# nm_main.net
KiCad netlist of a schematic drawn in Altium Designer
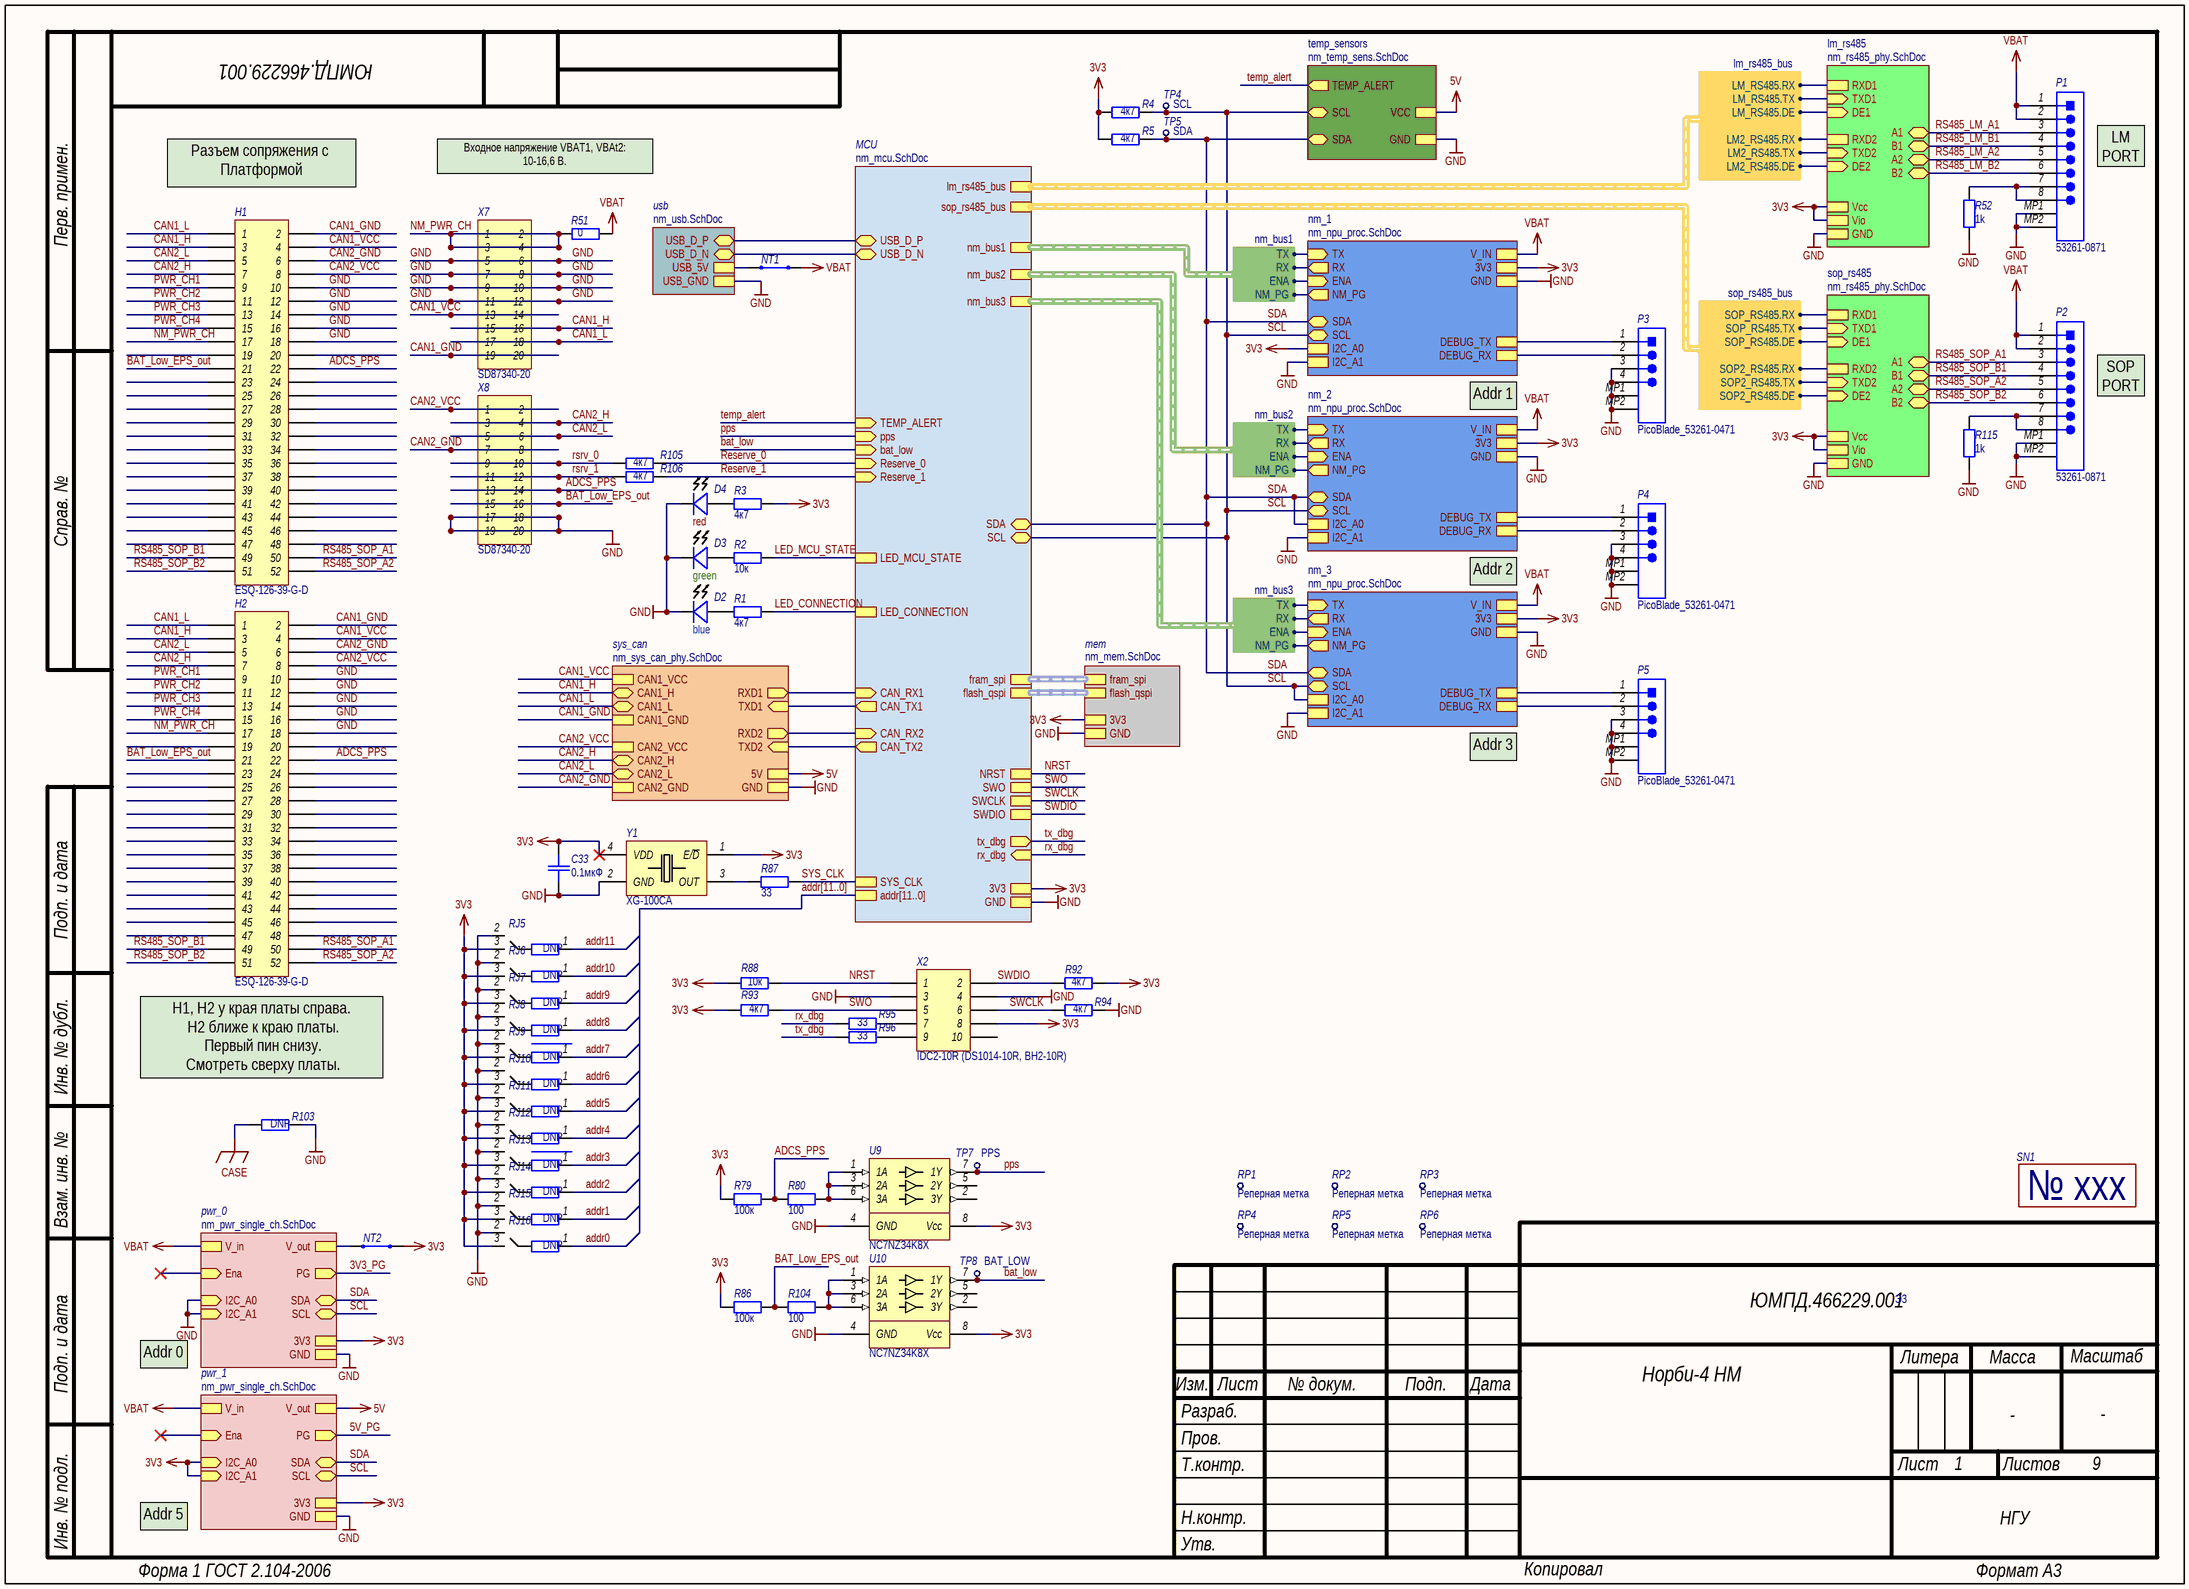
[diagram p0: nm_main.SchDoc]

(export (version "E")
  (design (tool "Eeschema 10.0.6"))
  (components
    (comp (ref "C33")
      (value "0.1мкФ")
      (footprint "SMD_C0603")
      (description "Capacitor")
      (libsource (lib "Passive") (part "Capacitor"))
    )
    (comp (ref "D2")
      (value "blue")
      (footprint "LED_0603")
      (fields (field (name "Comment") "LED"))
      (libsource (lib "LED") (part "LED"))
    )
    (comp (ref "D3")
      (value "green")
      (footprint "LED_0603")
      (fields (field (name "Comment") "LED"))
      (libsource (lib "LED") (part "LED"))
    )
    (comp (ref "D4")
      (value "red")
      (footprint "LED_0603")
      (fields (field (name "Comment") "LED"))
      (libsource (lib "LED") (part "LED"))
    )
    (comp (ref "H1")
      (value "ESQ-126-39-G-D")
      (footprint "ESQ-126-39-G-D")
      (description "Elevated socket, dual-row, 26-pin per row")
      (fields (field (name "НАИМЕНОВАНИЕ") "ESQ-126-39-G-D"))
      (libsource (lib "Connector") (part "ESQ-126-39-G-D"))
    )
    (comp (ref "H2")
      (value "ESQ-126-39-G-D")
      (footprint "ESQ-126-39-G-D")
      (description "Elevated socket, dual-row, 26-pin per row")
      (fields (field (name "НАИМЕНОВАНИЕ") "ESQ-126-39-G-D"))
      (libsource (lib "Connector") (part "ESQ-126-39-G-D"))
    )
    (comp (ref "NT1")
      (value "OSM R1-8")
      (footprint "NetTie_1mm")
      (description "Different Nets connection")
      (libsource (lib "Passive") (part "NetTie"))
    )
    (comp (ref "NT2")
      (value "OSM R1-8")
      (footprint "NetTie_1mm")
      (description "Different Nets connection")
      (libsource (lib "Passive") (part "NetTie"))
    )
    (comp (ref "P1")
      (value "53261-0871")
      (footprint "53261-0871")
      (description "Male Header, Pitch 1.25 mm, 1 x 8 Position, Height 3.4 mm, -40 to 85 degC, RoHS, Tape and Reel")
      (fields (field (name "НАИМЕНОВАНИЕ") "53261-0871"))
      (libsource (lib "Connector") (part "PicoBlade_53261-0871"))
    )
    (comp (ref "P2")
      (value "53261-0871")
      (footprint "53261-0871")
      (description "Male Header, Pitch 1.25 mm, 1 x 8 Position, Height 3.4 mm, -40 to 85 degC, RoHS, Tape and Reel")
      (fields (field (name "НАИМЕНОВАНИЕ") "53261-0871"))
      (libsource (lib "Connector") (part "PicoBlade_53261-0871"))
    )
    (comp (ref "P3")
      (value "PicoBlade_53261-0471")
      (footprint "53261-0471")
      (description "Male Header, Pitch 1.25 mm, 1 x 4 Position, Height 3.4 mm, -40 to 85 degC, RoHS, Tape and Reel")
      (libsource (lib "Connector") (part "PicoBlade_53261-0471"))
    )
    (comp (ref "P4")
      (value "PicoBlade_53261-0471")
      (footprint "53261-0471")
      (description "Male Header, Pitch 1.25 mm, 1 x 4 Position, Height 3.4 mm, -40 to 85 degC, RoHS, Tape and Reel")
      (libsource (lib "Connector") (part "PicoBlade_53261-0471"))
    )
    (comp (ref "P5")
      (value "PicoBlade_53261-0471")
      (footprint "53261-0471")
      (description "Male Header, Pitch 1.25 mm, 1 x 4 Position, Height 3.4 mm, -40 to 85 degC, RoHS, Tape and Reel")
      (libsource (lib "Connector") (part "PicoBlade_53261-0471"))
    )
    (comp (ref "R1")
      (value "4к7")
      (footprint "SMD_0603")
      (description "Resistor")
      (libsource (lib "") (part "Resistor_3"))
    )
    (comp (ref "R2")
      (value "10к")
      (footprint "SMD_0603")
      (description "Resistor")
      (libsource (lib "") (part "Resistor_3"))
    )
    (comp (ref "R3")
      (value "4к7")
      (footprint "SMD_0603")
      (description "Resistor")
      (libsource (lib "") (part "Resistor_3"))
    )
    (comp (ref "R4")
      (value "4к7")
      (footprint "SMD_0603")
      (description "Resistor")
      (libsource (lib "") (part "Resistor_1"))
    )
    (comp (ref "R5")
      (value "4к7")
      (footprint "SMD_0603")
      (description "Resistor")
      (libsource (lib "") (part "Resistor_1"))
    )
    (comp (ref "R51")
      (value "0")
      (footprint "SMD_1206")
      (description "Resistor")
      (libsource (lib "Passive") (part "Resistor"))
    )
    (comp (ref "R52")
      (value "1k")
      (footprint "SMD_0603")
      (description "Resistor")
      (libsource (lib "") (part "Resistor_2"))
    )
    (comp (ref "R79")
      (value "100к")
      (footprint "SMD_0603")
      (description "Resistor")
      (libsource (lib "Passive") (part "Resistor"))
    )
    (comp (ref "R80")
      (value "100")
      (footprint "SMD_0603")
      (description "Resistor")
      (libsource (lib "Passive") (part "Resistor"))
    )
    (comp (ref "R86")
      (value "100к")
      (footprint "SMD_0603")
      (description "Resistor")
      (libsource (lib "Passive") (part "Resistor"))
    )
    (comp (ref "R87")
      (value "33")
      (footprint "SMD_0603")
      (description "Resistor")
      (libsource (lib "") (part "Resistor_2"))
    )
    (comp (ref "R88")
      (value "10к")
      (footprint "SMD_0603")
      (description "Resistor")
      (libsource (lib "Passive") (part "Resistor"))
    )
    (comp (ref "R92")
      (value "4к7")
      (footprint "SMD_0603")
      (description "Resistor")
      (libsource (lib "") (part "Resistor_2"))
    )
    (comp (ref "R93")
      (value "4к7")
      (footprint "SMD_0603")
      (description "Resistor")
      (libsource (lib "") (part "Resistor_1"))
    )
    (comp (ref "R94")
      (value "4к7")
      (footprint "SMD_0603")
      (description "Resistor")
      (libsource (lib "") (part "Resistor_1"))
    )
    (comp (ref "R95")
      (value "33")
      (footprint "SMD_0603")
      (description "Resistor")
      (libsource (lib "") (part "Resistor_2"))
    )
    (comp (ref "R96")
      (value "33")
      (footprint "SMD_0603")
      (description "Resistor")
      (libsource (lib "") (part "Resistor_2"))
    )
    (comp (ref "R103")
      (value "DNP")
      (footprint "SMD_0805")
      (description "Resistor")
      (libsource (lib "") (part "Resistor_1"))
    )
    (comp (ref "R104")
      (value "100")
      (footprint "SMD_0603")
      (description "Resistor")
      (libsource (lib "Passive") (part "Resistor"))
    )
    (comp (ref "R105")
      (value "4к7")
      (footprint "SMD_0603")
      (description "Resistor")
      (libsource (lib "") (part "Resistor_3"))
    )
    (comp (ref "R106")
      (value "4к7")
      (footprint "SMD_0603")
      (description "Resistor")
      (libsource (lib "") (part "Resistor_3"))
    )
    (comp (ref "R115")
      (value "1k")
      (footprint "SMD_0603")
      (description "Resistor")
      (libsource (lib "") (part "Resistor_2"))
    )
    (comp (ref "RJ5")
      (value "DNP")
      (footprint "SMD_JMP_0402")
      (description "Resistor-Jumper")
      (fields (field (name "Comment") "OSM R1-8"))
      (libsource (lib "Passive") (part "Resistor_Jamper"))
    )
    (comp (ref "RJ6")
      (value "DNP")
      (footprint "SMD_JMP_0402")
      (description "Resistor-Jumper")
      (fields (field (name "Comment") "OSM R1-8"))
      (libsource (lib "Passive") (part "Resistor_Jamper"))
    )
    (comp (ref "RJ7")
      (value "DNP")
      (footprint "SMD_JMP_0402")
      (description "Resistor-Jumper")
      (fields (field (name "Comment") "OSM R1-8"))
      (libsource (lib "Passive") (part "Resistor_Jamper"))
    )
    (comp (ref "RJ8")
      (value "DNP")
      (footprint "SMD_JMP_0402")
      (description "Resistor-Jumper")
      (fields (field (name "Comment") "OSM R1-8"))
      (libsource (lib "Passive") (part "Resistor_Jamper"))
    )
    (comp (ref "RJ9")
      (value "DNP")
      (footprint "SMD_JMP_0402")
      (description "Resistor-Jumper")
      (fields (field (name "Comment") "OSM R1-8"))
      (libsource (lib "Passive") (part "Resistor_Jamper"))
    )
    (comp (ref "RJ10")
      (value "DNP")
      (footprint "SMD_JMP_0402")
      (description "Resistor-Jumper")
      (fields (field (name "Comment") "OSM R1-8"))
      (libsource (lib "Passive") (part "Resistor_Jamper"))
    )
    (comp (ref "RJ11")
      (value "DNP")
      (footprint "SMD_JMP_0402")
      (description "Resistor-Jumper")
      (fields (field (name "Comment") "OSM R1-8"))
      (libsource (lib "Passive") (part "Resistor_Jamper"))
    )
    (comp (ref "RJ12")
      (value "DNP")
      (footprint "SMD_JMP_0402")
      (description "Resistor-Jumper")
      (fields (field (name "Comment") "OSM R1-8"))
      (libsource (lib "Passive") (part "Resistor_Jamper"))
    )
    (comp (ref "RJ13")
      (value "DNP")
      (footprint "SMD_JMP_0402")
      (description "Resistor-Jumper")
      (fields (field (name "Comment") "OSM R1-8"))
      (libsource (lib "Passive") (part "Resistor_Jamper"))
    )
    (comp (ref "RJ14")
      (value "DNP")
      (footprint "SMD_JMP_0402")
      (description "Resistor-Jumper")
      (fields (field (name "Comment") "OSM R1-8"))
      (libsource (lib "Passive") (part "Resistor_Jamper"))
    )
    (comp (ref "RJ15")
      (value "DNP")
      (footprint "SMD_JMP_0402")
      (description "Resistor-Jumper")
      (fields (field (name "Comment") "OSM R1-8"))
      (libsource (lib "Passive") (part "Resistor_Jamper"))
    )
    (comp (ref "RJ16")
      (value "DNP")
      (footprint "SMD_JMP_0402")
      (description "Resistor-Jumper")
      (fields (field (name "Comment") "OSM R1-8"))
      (libsource (lib "Passive") (part "Resistor_Jamper"))
    )
    (comp (ref "RP1")
      (value "RP")
      (footprint "ReperPoint")
      (fields (field (name "НАИМЕНОВАНИЕ") "Реперная метка"))
      (libsource (lib "Connector") (part "RP"))
    )
    (comp (ref "RP2")
      (value "RP")
      (footprint "ReperPoint")
      (fields (field (name "НАИМЕНОВАНИЕ") "Реперная метка"))
      (libsource (lib "Connector") (part "RP"))
    )
    (comp (ref "RP3")
      (value "RP")
      (footprint "ReperPoint")
      (fields (field (name "НАИМЕНОВАНИЕ") "Реперная метка"))
      (libsource (lib "Connector") (part "RP"))
    )
    (comp (ref "RP4")
      (value "RP")
      (footprint "ReperPoint")
      (fields (field (name "НАИМЕНОВАНИЕ") "Реперная метка"))
      (libsource (lib "Connector") (part "RP"))
    )
    (comp (ref "RP5")
      (value "RP")
      (footprint "ReperPoint")
      (fields (field (name "НАИМЕНОВАНИЕ") "Реперная метка"))
      (libsource (lib "Connector") (part "RP"))
    )
    (comp (ref "RP6")
      (value "RP")
      (footprint "ReperPoint")
      (fields (field (name "НАИМЕНОВАНИЕ") "Реперная метка"))
      (libsource (lib "Connector") (part "RP"))
    )
    (comp (ref "SN1")
      (value "Место под нанесение серийного номера")
      (footprint "Serial_number_v2")
      (libsource (lib "Serial_number") (part "Serial_number"))
    )
    (comp (ref "TP4")
      (value "SCL")
      (footprint "TP_PAD_1")
      (fields (field (name "TP_NAME") "SCL"))
      (libsource (lib "Connector") (part "TP"))
    )
    (comp (ref "TP5")
      (value "SDA")
      (footprint "TP_PAD_1")
      (fields (field (name "TP_NAME") "SDA"))
      (libsource (lib "Connector") (part "TP"))
    )
    (comp (ref "TP7")
      (value "PPS")
      (footprint "TP_PAD_1")
      (fields (field (name "TP_NAME") "PPS"))
      (libsource (lib "Connector") (part "TP"))
    )
    (comp (ref "TP8")
      (value "BAT_LOW")
      (footprint "TP_PAD_1")
      (fields (field (name "TP_NAME") "BAT_LOW"))
      (libsource (lib "Connector") (part "TP"))
    )
    (comp (ref "U9")
      (value "NC7NZ34")
      (footprint "US-8")
      (description "TinyLogic UHS Triple Buffer")
      (fields (field (name "НАИМЕНОВАНИЕ") "NC7NZ34K8X"))
      (libsource (lib "Logic") (part "NC7NZ34"))
    )
    (comp (ref "U10")
      (value "NC7NZ34")
      (footprint "US-8")
      (description "TinyLogic UHS Triple Buffer")
      (fields (field (name "НАИМЕНОВАНИЕ") "NC7NZ34K8X"))
      (libsource (lib "Logic") (part "NC7NZ34"))
    )
    (comp (ref "X2")
      (value "Header 2X10")
      (footprint "IDC2-10R")
      (description "Header, 10-Pin, Dual row")
      (fields (field (name "НАИМЕНОВАНИЕ") "IDC2-10R (DS1014-10R, BH2-10R)"))
      (libsource (lib "Header 2X10") (part "Header 2X10"))
    )
    (comp (ref "X7")
      (value "Header 2X20")
      (footprint "PLD2-20_SD87340-20")
      (description "Header, 20-Pin, Dual row")
      (fields (field (name "НАИМЕНОВАНИЕ") "SD87340-20"))
      (libsource (lib "Connector") (part "Header 2X20"))
    )
    (comp (ref "X8")
      (value "Header 2X20")
      (footprint "PLD2-20_SD87340-20")
      (description "Header, 20-Pin, Dual row")
      (fields (field (name "НАИМЕНОВАНИЕ") "SD87340-20"))
      (libsource (lib "Connector") (part "Header 2X20"))
    )
    (comp (ref "Y1")
      (value "XG-1000CA")
      (footprint "SMD_7050_Crystal_Oscillator")
      (description "Crystall oscillator, CMOS, 3.3V, SMD7050")
      (fields (field (name "НАИМЕНОВАНИЕ") "XG-100CA"))
      (libsource (lib "Oscillator") (part "Crystal_Oscillator"))
    )
  )
  (nets
    (net (code "8") (name "/ADCS_PPS") (class "Default")
      (node (ref "H1") (pin "22") (pinfunction "22_22") (pintype "passive"))
      (node (ref "H2") (pin "22") (pinfunction "22_22") (pintype "passive"))
      (node (ref "R79") (pin "2") (pinfunction "2_2") (pintype "passive"))
      (node (ref "R80") (pin "1") (pinfunction "1_1") (pintype "passive"))
      (node (ref "X8") (pin "13") (pinfunction "13_13") (pintype "passive"))
      (node (ref "X8") (pin "14") (pinfunction "14_14") (pintype "passive"))
    )
    (net (code "9") (name "/BAT_Low_EPS_out") (class "Default")
      (node (ref "H1") (pin "21") (pinfunction "21_21") (pintype "passive"))
      (node (ref "H2") (pin "21") (pinfunction "21_21") (pintype "passive"))
      (node (ref "R104") (pin "1") (pinfunction "1_1") (pintype "passive"))
      (node (ref "R86") (pin "2") (pinfunction "2_2") (pintype "passive"))
      (node (ref "X8") (pin "15") (pinfunction "15_15") (pintype "passive"))
      (node (ref "X8") (pin "16") (pinfunction "16_16") (pintype "passive"))
    )
    (net (code "10") (name "/CAN1_GND") (class "Default")
      (node (ref "H1") (pin "2") (pinfunction "2_2") (pintype "passive"))
      (node (ref "H2") (pin "2") (pinfunction "2_2") (pintype "passive"))
      (node (ref "X7") (pin "19") (pinfunction "19_19") (pintype "passive"))
      (node (ref "X7") (pin "20") (pinfunction "20_20") (pintype "passive"))
    )
    (net (code "11") (name "/CAN1_H") (class "Default")
      (node (ref "H1") (pin "3") (pinfunction "3_3") (pintype "passive"))
      (node (ref "H2") (pin "3") (pinfunction "3_3") (pintype "passive"))
      (node (ref "X7") (pin "15") (pinfunction "15_15") (pintype "passive"))
      (node (ref "X7") (pin "16") (pinfunction "16_16") (pintype "passive"))
    )
    (net (code "12") (name "/CAN1_L") (class "Default")
      (node (ref "H1") (pin "1") (pinfunction "1_1") (pintype "passive"))
      (node (ref "H2") (pin "1") (pinfunction "1_1") (pintype "passive"))
      (node (ref "X7") (pin "17") (pinfunction "17_17") (pintype "passive"))
      (node (ref "X7") (pin "18") (pinfunction "18_18") (pintype "passive"))
    )
    (net (code "13") (name "/CAN1_VCC") (class "Default")
      (node (ref "H1") (pin "4") (pinfunction "4_4") (pintype "passive"))
      (node (ref "H2") (pin "4") (pinfunction "4_4") (pintype "passive"))
      (node (ref "X7") (pin "13") (pinfunction "13_13") (pintype "passive"))
      (node (ref "X7") (pin "14") (pinfunction "14_14") (pintype "passive"))
    )
    (net (code "14") (name "/CAN2_GND") (class "Default")
      (node (ref "H1") (pin "6") (pinfunction "6_6") (pintype "passive"))
      (node (ref "H2") (pin "6") (pinfunction "6_6") (pintype "passive"))
      (node (ref "X8") (pin "7") (pinfunction "7_7") (pintype "passive"))
      (node (ref "X8") (pin "8") (pinfunction "8_8") (pintype "passive"))
    )
    (net (code "15") (name "/CAN2_H") (class "Default")
      (node (ref "H1") (pin "7") (pinfunction "7_7") (pintype "passive"))
      (node (ref "H2") (pin "7") (pinfunction "7_7") (pintype "passive"))
      (node (ref "X8") (pin "3") (pinfunction "3_3") (pintype "passive"))
      (node (ref "X8") (pin "4") (pinfunction "4_4") (pintype "passive"))
    )
    (net (code "16") (name "/CAN2_L") (class "Default")
      (node (ref "H1") (pin "5") (pinfunction "5_5") (pintype "passive"))
      (node (ref "H2") (pin "5") (pinfunction "5_5") (pintype "passive"))
      (node (ref "X8") (pin "5") (pinfunction "5_5") (pintype "passive"))
      (node (ref "X8") (pin "6") (pinfunction "6_6") (pintype "passive"))
    )
    (net (code "17") (name "/CAN2_VCC") (class "Default")
      (node (ref "H1") (pin "8") (pinfunction "8_8") (pintype "passive"))
      (node (ref "H2") (pin "8") (pinfunction "8_8") (pintype "passive"))
      (node (ref "X8") (pin "1") (pinfunction "1_1") (pintype "passive"))
      (node (ref "X8") (pin "2") (pinfunction "2_2") (pintype "passive"))
    )
    (net (code "24") (name "/DEBUG_RX") (class "Default")
      (node (ref "P5") (pin "2") (pinfunction "2_2") (pintype "passive"))
    )
    (net (code "25") (name "/DEBUG_RX_1") (class "Default")
      (node (ref "P4") (pin "2") (pinfunction "2_2") (pintype "passive"))
    )
    (net (code "26") (name "/DEBUG_RX_2") (class "Default")
      (node (ref "P3") (pin "2") (pinfunction "2_2") (pintype "passive"))
    )
    (net (code "27") (name "/DEBUG_TX") (class "Default")
      (node (ref "P3") (pin "1") (pinfunction "1_1") (pintype "passive"))
    )
    (net (code "28") (name "/DEBUG_TX_1") (class "Default")
      (node (ref "P4") (pin "1") (pinfunction "1_1") (pintype "passive"))
    )
    (net (code "29") (name "/DEBUG_TX_2") (class "Default")
      (node (ref "P5") (pin "1") (pinfunction "1_1") (pintype "passive"))
    )
    (net (code "35") (name "/LED_CONNECTION") (class "Default")
      (node (ref "R1") (pin "1") (pinfunction "1_1") (pintype "passive"))
    )
    (net (code "36") (name "/LED_MCU_STATE") (class "Default")
      (node (ref "R2") (pin "1") (pinfunction "1_1") (pintype "passive"))
    )
    (net (code "40") (name "/NM_PWR_CH") (class "Default")
      (node (ref "H1") (pin "17") (pinfunction "17_17") (pintype "passive"))
      (node (ref "H2") (pin "17") (pinfunction "17_17") (pintype "passive"))
      (node (ref "R51") (pin "1") (pinfunction "1_1") (pintype "passive"))
      (node (ref "X7") (pin "1") (pinfunction "1_1") (pintype "passive"))
      (node (ref "X7") (pin "2") (pinfunction "2_2") (pintype "passive"))
      (node (ref "X7") (pin "3") (pinfunction "3_3") (pintype "passive"))
      (node (ref "X7") (pin "4") (pinfunction "4_4") (pintype "passive"))
    )
    (net (code "41") (name "/NRST") (class "Default")
      (node (ref "R88") (pin "2") (pinfunction "2_2") (pintype "passive"))
      (node (ref "X2") (pin "1") (pinfunction "1_1") (pintype "passive"))
    )
    (net (code "42") (name "/PWR_CH1") (class "Default")
      (node (ref "H1") (pin "9") (pinfunction "9_9") (pintype "passive"))
      (node (ref "H2") (pin "9") (pinfunction "9_9") (pintype "passive"))
    )
    (net (code "43") (name "/PWR_CH2") (class "Default")
      (node (ref "H1") (pin "11") (pinfunction "11_11") (pintype "passive"))
      (node (ref "H2") (pin "11") (pinfunction "11_11") (pintype "passive"))
    )
    (net (code "44") (name "/PWR_CH3") (class "Default")
      (node (ref "H1") (pin "13") (pinfunction "13_13") (pintype "passive"))
      (node (ref "H2") (pin "13") (pinfunction "13_13") (pintype "passive"))
    )
    (net (code "45") (name "/PWR_CH4") (class "Default")
      (node (ref "H1") (pin "15") (pinfunction "15_15") (pintype "passive"))
      (node (ref "H2") (pin "15") (pinfunction "15_15") (pintype "passive"))
    )
    (net (code "46") (name "/RS485_LM_A1") (class "Default")
      (node (ref "P1") (pin "3") (pinfunction "3_3") (pintype "passive"))
    )
    (net (code "47") (name "/RS485_LM_A2") (class "Default")
      (node (ref "P1") (pin "5") (pinfunction "5_5") (pintype "passive"))
    )
    (net (code "48") (name "/RS485_LM_B1") (class "Default")
      (node (ref "P1") (pin "4") (pinfunction "4_4") (pintype "passive"))
    )
    (net (code "49") (name "/RS485_LM_B2") (class "Default")
      (node (ref "P1") (pin "6") (pinfunction "6_6") (pintype "passive"))
    )
    (net (code "50") (name "/RS485_SOP_A1") (class "Default")
      (node (ref "H1") (pin "50") (pinfunction "50_50") (pintype "passive"))
      (node (ref "H2") (pin "50") (pinfunction "50_50") (pintype "passive"))
      (node (ref "P2") (pin "3") (pinfunction "3_3") (pintype "passive"))
    )
    (net (code "51") (name "/RS485_SOP_A2") (class "Default")
      (node (ref "H1") (pin "52") (pinfunction "52_52") (pintype "passive"))
      (node (ref "H2") (pin "52") (pinfunction "52_52") (pintype "passive"))
      (node (ref "P2") (pin "5") (pinfunction "5_5") (pintype "passive"))
    )
    (net (code "52") (name "/RS485_SOP_B1") (class "Default")
      (node (ref "H1") (pin "49") (pinfunction "49_49") (pintype "passive"))
      (node (ref "H2") (pin "49") (pinfunction "49_49") (pintype "passive"))
      (node (ref "P2") (pin "4") (pinfunction "4_4") (pintype "passive"))
    )
    (net (code "53") (name "/RS485_SOP_B2") (class "Default")
      (node (ref "H1") (pin "51") (pinfunction "51_51") (pintype "passive"))
      (node (ref "H2") (pin "51") (pinfunction "51_51") (pintype "passive"))
      (node (ref "P2") (pin "6") (pinfunction "6_6") (pintype "passive"))
    )
    (net (code "63") (name "/Reserve_0") (class "Default")
      (node (ref "R105") (pin "1") (pinfunction "1_1") (pintype "passive"))
    )
    (net (code "64") (name "/Reserve_1") (class "Default")
      (node (ref "R106") (pin "1") (pinfunction "1_1") (pintype "passive"))
    )
    (net (code "65") (name "/SCL") (class "Default")
      (node (ref "R4") (pin "1") (pinfunction "1_1") (pintype "passive"))
      (node (ref "TP4") (pin "0") (pinfunction "TP_0") (pintype "passive"))
    )
    (net (code "66") (name "/SDA") (class "Default")
      (node (ref "R5") (pin "1") (pinfunction "1_1") (pintype "passive"))
      (node (ref "TP5") (pin "0") (pinfunction "TP_0") (pintype "passive"))
    )
    (net (code "67") (name "/SWCLK") (class "Default")
      (node (ref "R94") (pin "2") (pinfunction "2_2") (pintype "passive"))
      (node (ref "X2") (pin "6") (pinfunction "6_6") (pintype "passive"))
    )
    (net (code "68") (name "/SWDIO") (class "Default")
      (node (ref "R92") (pin "1") (pinfunction "1_1") (pintype "passive"))
      (node (ref "X2") (pin "2") (pinfunction "2_2") (pintype "passive"))
    )
    (net (code "69") (name "/SWO") (class "Default")
      (node (ref "R93") (pin "1") (pinfunction "1_1") (pintype "passive"))
      (node (ref "X2") (pin "5") (pinfunction "5_5") (pintype "passive"))
    )
    (net (code "70") (name "/SYS_CLK") (class "Default")
      (node (ref "R87") (pin "2") (pinfunction "2_2") (pintype "passive"))
    )
    (net (code "78") (name "/USB_5V") (class "Default")
      (node (ref "NT1") (pin "1") (pinfunction "1_1") (pintype "passive"))
    )
    (net (code "81") (name "/V_out") (class "Default")
      (node (ref "NT2") (pin "1") (pinfunction "1_1") (pintype "passive"))
    )
    (net (code "82") (name "/addr0") (class "Default") (node (ref "RJ16") (pin "1") (pintype "passive")))
    (net (code "83") (name "/addr1") (class "Default") (node (ref "RJ15") (pin "1") (pintype "passive")))
    (net (code "84") (name "/addr2") (class "Default") (node (ref "RJ14") (pin "1") (pintype "passive")))
    (net (code "85") (name "/addr3") (class "Default") (node (ref "RJ13") (pin "1") (pintype "passive")))
    (net (code "86") (name "/addr4") (class "Default") (node (ref "RJ12") (pin "1") (pintype "passive")))
    (net (code "87") (name "/addr5") (class "Default") (node (ref "RJ11") (pin "1") (pintype "passive")))
    (net (code "88") (name "/addr6") (class "Default") (node (ref "RJ10") (pin "1") (pintype "passive")))
    (net (code "89") (name "/addr7") (class "Default") (node (ref "RJ9") (pin "1") (pintype "passive")))
    (net (code "90") (name "/addr8") (class "Default") (node (ref "RJ8") (pin "1") (pintype "passive")))
    (net (code "91") (name "/addr9") (class "Default") (node (ref "RJ7") (pin "1") (pintype "passive")))
    (net (code "92") (name "/addr10") (class "Default") (node (ref "RJ6") (pin "1") (pintype "passive")))
    (net (code "93") (name "/addr11") (class "Default") (node (ref "RJ5") (pin "1") (pintype "passive")))
    (net (code "95") (name "/bat_low") (class "Default")
      (node (ref "TP8") (pin "0") (pinfunction "TP_0") (pintype "passive"))
      (node (ref "U10") (pin "7") (pinfunction "1Y_7") (pintype "output"))
    )
    (net (code "98") (name "/pps") (class "Default")
      (node (ref "TP7") (pin "0") (pinfunction "TP_0") (pintype "passive"))
      (node (ref "U9") (pin "7") (pinfunction "1Y_7") (pintype "output"))
    )
    (net (code "99") (name "/rsrv_0") (class "Default")
      (node (ref "R105") (pin "2") (pinfunction "2_2") (pintype "passive"))
      (node (ref "X8") (pin "10") (pinfunction "10_10") (pintype "passive"))
      (node (ref "X8") (pin "9") (pinfunction "9_9") (pintype "passive"))
    )
    (net (code "100") (name "/rsrv_1") (class "Default")
      (node (ref "R106") (pin "2") (pinfunction "2_2") (pintype "passive"))
      (node (ref "X8") (pin "11") (pinfunction "11_11") (pintype "passive"))
      (node (ref "X8") (pin "12") (pinfunction "12_12") (pintype "passive"))
    )
    (net (code "101") (name "/rx_dbg") (class "Default")
      (node (ref "R95") (pin "1") (pinfunction "1_1") (pintype "passive"))
    )
    (net (code "103") (name "/tx_dbg") (class "Default")
      (node (ref "R96") (pin "1") (pinfunction "1_1") (pintype "passive"))
    )
    (net (code "109") (name "3V3") (class "Default")
      (node (ref "C33") (pin "2") (pinfunction "2_2") (pintype "passive"))
      (node (ref "NT2") (pin "2") (pinfunction "2_2") (pintype "passive"))
      (node (ref "R3") (pin "1") (pinfunction "1_1") (pintype "passive"))
      (node (ref "R4") (pin "2") (pinfunction "2_2") (pintype "passive"))
      (node (ref "R5") (pin "2") (pinfunction "2_2") (pintype "passive"))
      (node (ref "R79") (pin "1") (pinfunction "1_1") (pintype "passive"))
      (node (ref "R86") (pin "1") (pinfunction "1_1") (pintype "passive"))
      (node (ref "R88") (pin "1") (pinfunction "1_1") (pintype "passive"))
      (node (ref "R92") (pin "2") (pinfunction "2_2") (pintype "passive"))
      (node (ref "R93") (pin "2") (pinfunction "2_2") (pintype "passive"))
      (node (ref "RJ10") (pin "3") (pintype "passive"))
      (node (ref "RJ11") (pin "3") (pintype "passive"))
      (node (ref "RJ12") (pin "3") (pintype "passive"))
      (node (ref "RJ13") (pin "3") (pintype "passive"))
      (node (ref "RJ14") (pin "3") (pintype "passive"))
      (node (ref "RJ15") (pin "3") (pintype "passive"))
      (node (ref "RJ16") (pin "3") (pintype "passive"))
      (node (ref "RJ5") (pin "3") (pintype "passive"))
      (node (ref "RJ6") (pin "3") (pintype "passive"))
      (node (ref "RJ7") (pin "3") (pintype "passive"))
      (node (ref "RJ8") (pin "3") (pintype "passive"))
      (node (ref "RJ9") (pin "3") (pintype "passive"))
      (node (ref "U10") (pin "8") (pinfunction "Vcc_8") (pintype "power_in"))
      (node (ref "U9") (pin "8") (pinfunction "Vcc_8") (pintype "power_in"))
      (node (ref "X2") (pin "8") (pinfunction "8_8") (pintype "passive"))
      (node (ref "Y1") (pin "1") (pinfunction "E/~{D}_1") (pintype "passive"))
      (node (ref "Y1") (pin "4") (pinfunction "VDD_4") (pintype "passive"))
    )
    (net (code "111") (name "CASE") (class "Default")
      (node (ref "R103") (pin "2") (pinfunction "2_2") (pintype "passive"))
    )
    (net (code "112") (name "GND") (class "Default")
      (node (ref "C33") (pin "1") (pinfunction "1_1") (pintype "passive"))
      (node (ref "D2") (pin "2") (pinfunction "K_2") (pintype "passive"))
      (node (ref "D3") (pin "2") (pinfunction "K_2") (pintype "passive"))
      (node (ref "D4") (pin "2") (pinfunction "K_2") (pintype "passive"))
      (node (ref "H1") (pin "10") (pinfunction "10_10") (pintype "passive"))
      (node (ref "H1") (pin "12") (pinfunction "12_12") (pintype "passive"))
      (node (ref "H1") (pin "14") (pinfunction "14_14") (pintype "passive"))
      (node (ref "H1") (pin "16") (pinfunction "16_16") (pintype "passive"))
      (node (ref "H1") (pin "18") (pinfunction "18_18") (pintype "passive"))
      (node (ref "H2") (pin "10") (pinfunction "10_10") (pintype "passive"))
      (node (ref "H2") (pin "12") (pinfunction "12_12") (pintype "passive"))
      (node (ref "H2") (pin "14") (pinfunction "14_14") (pintype "passive"))
      (node (ref "H2") (pin "16") (pinfunction "16_16") (pintype "passive"))
      (node (ref "H2") (pin "18") (pinfunction "18_18") (pintype "passive"))
      (node (ref "P1") (pin "MP1") (pinfunction "MP1_MP1") (pintype "passive"))
      (node (ref "P1") (pin "MP2") (pinfunction "MP2_MP2") (pintype "passive"))
      (node (ref "P2") (pin "MP1") (pinfunction "MP1_MP1") (pintype "passive"))
      (node (ref "P2") (pin "MP2") (pinfunction "MP2_MP2") (pintype "passive"))
      (node (ref "P3") (pin "3") (pinfunction "3_3") (pintype "passive"))
      (node (ref "P3") (pin "4") (pinfunction "4_4") (pintype "passive"))
      (node (ref "P3") (pin "MP1") (pinfunction "MP1_MP1") (pintype "passive"))
      (node (ref "P3") (pin "MP2") (pinfunction "MP2_MP2") (pintype "passive"))
      (node (ref "P4") (pin "3") (pinfunction "3_3") (pintype "passive"))
      (node (ref "P4") (pin "4") (pinfunction "4_4") (pintype "passive"))
      (node (ref "P4") (pin "MP1") (pinfunction "MP1_MP1") (pintype "passive"))
      (node (ref "P4") (pin "MP2") (pinfunction "MP2_MP2") (pintype "passive"))
      (node (ref "P5") (pin "3") (pinfunction "3_3") (pintype "passive"))
      (node (ref "P5") (pin "4") (pinfunction "4_4") (pintype "passive"))
      (node (ref "P5") (pin "MP1") (pinfunction "MP1_MP1") (pintype "passive"))
      (node (ref "P5") (pin "MP2") (pinfunction "MP2_MP2") (pintype "passive"))
      (node (ref "R103") (pin "1") (pinfunction "1_1") (pintype "passive"))
      (node (ref "R115") (pin "1") (pinfunction "1_1") (pintype "passive"))
      (node (ref "R52") (pin "1") (pinfunction "1_1") (pintype "passive"))
      (node (ref "R94") (pin "1") (pinfunction "1_1") (pintype "passive"))
      (node (ref "RJ10") (pin "2") (pintype "passive"))
      (node (ref "RJ11") (pin "2") (pintype "passive"))
      (node (ref "RJ12") (pin "2") (pintype "passive"))
      (node (ref "RJ13") (pin "2") (pintype "passive"))
      (node (ref "RJ14") (pin "2") (pintype "passive"))
      (node (ref "RJ15") (pin "2") (pintype "passive"))
      (node (ref "RJ16") (pin "2") (pintype "passive"))
      (node (ref "RJ5") (pin "2") (pintype "passive"))
      (node (ref "RJ6") (pin "2") (pintype "passive"))
      (node (ref "RJ7") (pin "2") (pintype "passive"))
      (node (ref "RJ8") (pin "2") (pintype "passive"))
      (node (ref "RJ9") (pin "2") (pintype "passive"))
      (node (ref "U10") (pin "4") (pinfunction "GND_4") (pintype "power_in"))
      (node (ref "U9") (pin "4") (pinfunction "GND_4") (pintype "power_in"))
      (node (ref "X2") (pin "3") (pinfunction "3_3") (pintype "passive"))
      (node (ref "X2") (pin "4") (pinfunction "4_4") (pintype "passive"))
      (node (ref "X7") (pin "10") (pinfunction "10_10") (pintype "passive"))
      (node (ref "X7") (pin "11") (pinfunction "11_11") (pintype "passive"))
      (node (ref "X7") (pin "12") (pinfunction "12_12") (pintype "passive"))
      (node (ref "X7") (pin "5") (pinfunction "5_5") (pintype "passive"))
      (node (ref "X7") (pin "6") (pinfunction "6_6") (pintype "passive"))
      (node (ref "X7") (pin "7") (pinfunction "7_7") (pintype "passive"))
      (node (ref "X7") (pin "8") (pinfunction "8_8") (pintype "passive"))
      (node (ref "X7") (pin "9") (pinfunction "9_9") (pintype "passive"))
      (node (ref "X8") (pin "17") (pinfunction "17_17") (pintype "passive"))
      (node (ref "X8") (pin "18") (pinfunction "18_18") (pintype "passive"))
      (node (ref "X8") (pin "19") (pinfunction "19_19") (pintype "passive"))
      (node (ref "X8") (pin "20") (pinfunction "20_20") (pintype "passive"))
      (node (ref "Y1") (pin "2") (pinfunction "GND_2") (pintype "passive"))
    )
    (net (code "113") (name "Net-(D2-A)") (class "Default")
      (node (ref "D2") (pin "1") (pinfunction "A_1") (pintype "passive"))
      (node (ref "R1") (pin "2") (pinfunction "2_2") (pintype "passive"))
    )
    (net (code "114") (name "Net-(D3-A)") (class "Default")
      (node (ref "D3") (pin "1") (pinfunction "A_1") (pintype "passive"))
      (node (ref "R2") (pin "2") (pinfunction "2_2") (pintype "passive"))
    )
    (net (code "115") (name "Net-(D4-A)") (class "Default")
      (node (ref "D4") (pin "1") (pinfunction "A_1") (pintype "passive"))
      (node (ref "R3") (pin "2") (pinfunction "2_2") (pintype "passive"))
    )
    (net (code "116") (name "Net-(P1-Pad7)") (class "Default")
      (node (ref "P1") (pin "7") (pinfunction "7_7") (pintype "passive"))
      (node (ref "P1") (pin "8") (pinfunction "8_8") (pintype "passive"))
      (node (ref "R52") (pin "2") (pinfunction "2_2") (pintype "passive"))
    )
    (net (code "117") (name "Net-(P2-Pad7)") (class "Default")
      (node (ref "P2") (pin "7") (pinfunction "7_7") (pintype "passive"))
      (node (ref "P2") (pin "8") (pinfunction "8_8") (pintype "passive"))
      (node (ref "R115") (pin "2") (pinfunction "2_2") (pintype "passive"))
    )
    (net (code "118") (name "Net-(R95-Pad2)") (class "Default")
      (node (ref "R95") (pin "2") (pinfunction "2_2") (pintype "passive"))
      (node (ref "X2") (pin "7") (pinfunction "7_7") (pintype "passive"))
    )
    (net (code "119") (name "Net-(R96-Pad2)") (class "Default")
      (node (ref "R96") (pin "2") (pinfunction "2_2") (pintype "passive"))
      (node (ref "X2") (pin "9") (pinfunction "9_9") (pintype "passive"))
    )
    (net (code "120") (name "Net-(U9-1A)") (class "Default")
      (node (ref "R80") (pin "2") (pinfunction "2_2") (pintype "passive"))
      (node (ref "U9") (pin "1") (pinfunction "1A_1") (pintype "input"))
      (node (ref "U9") (pin "3") (pinfunction "2A_3") (pintype "input"))
      (node (ref "U9") (pin "6") (pinfunction "3A_6") (pintype "input"))
    )
    (net (code "121") (name "Net-(U10-1A)") (class "Default")
      (node (ref "R104") (pin "2") (pinfunction "2_2") (pintype "passive"))
      (node (ref "U10") (pin "1") (pinfunction "1A_1") (pintype "input"))
      (node (ref "U10") (pin "3") (pinfunction "2A_3") (pintype "input"))
      (node (ref "U10") (pin "6") (pinfunction "3A_6") (pintype "input"))
    )
    (net (code "122") (name "Net-(Y1-OUT)") (class "Default")
      (node (ref "R87") (pin "1") (pinfunction "1_1") (pintype "passive"))
      (node (ref "Y1") (pin "3") (pinfunction "OUT_3") (pintype "passive"))
    )
    (net (code "123") (name "VBAT") (class "Default")
      (node (ref "NT1") (pin "2") (pinfunction "2_2") (pintype "passive"))
      (node (ref "P1") (pin "1") (pinfunction "1_1") (pintype "passive"))
      (node (ref "P1") (pin "2") (pinfunction "2_2") (pintype "passive"))
      (node (ref "P2") (pin "1") (pinfunction "1_1") (pintype "passive"))
      (node (ref "P2") (pin "2") (pinfunction "2_2") (pintype "passive"))
      (node (ref "R51") (pin "2") (pinfunction "2_2") (pintype "passive"))
    )
    (net (code "124") (name "unconnected-(H1-Pad19)") (class "Default")
      (node (ref "H1") (pin "19") (pinfunction "19_19") (pintype "passive"))
    )
    (net (code "125") (name "unconnected-(H1-Pad20)") (class "Default")
      (node (ref "H1") (pin "20") (pinfunction "20_20") (pintype "passive"))
    )
    (net (code "126") (name "unconnected-(H1-Pad23)") (class "Default")
      (node (ref "H1") (pin "23") (pinfunction "23_23") (pintype "passive"))
    )
    (net (code "127") (name "unconnected-(H1-Pad24)") (class "Default")
      (node (ref "H1") (pin "24") (pinfunction "24_24") (pintype "passive"))
    )
    (net (code "128") (name "unconnected-(H1-Pad25)") (class "Default")
      (node (ref "H1") (pin "25") (pinfunction "25_25") (pintype "passive"))
    )
    (net (code "129") (name "unconnected-(H1-Pad26)") (class "Default")
      (node (ref "H1") (pin "26") (pinfunction "26_26") (pintype "passive"))
    )
    (net (code "130") (name "unconnected-(H1-Pad27)") (class "Default")
      (node (ref "H1") (pin "27") (pinfunction "27_27") (pintype "passive"))
    )
    (net (code "131") (name "unconnected-(H1-Pad28)") (class "Default")
      (node (ref "H1") (pin "28") (pinfunction "28_28") (pintype "passive"))
    )
    (net (code "132") (name "unconnected-(H1-Pad29)") (class "Default")
      (node (ref "H1") (pin "29") (pinfunction "29_29") (pintype "passive"))
    )
    (net (code "133") (name "unconnected-(H1-Pad30)") (class "Default")
      (node (ref "H1") (pin "30") (pinfunction "30_30") (pintype "passive"))
    )
    (net (code "134") (name "unconnected-(H1-Pad31)") (class "Default")
      (node (ref "H1") (pin "31") (pinfunction "31_31") (pintype "passive"))
    )
    (net (code "135") (name "unconnected-(H1-Pad32)") (class "Default")
      (node (ref "H1") (pin "32") (pinfunction "32_32") (pintype "passive"))
    )
    (net (code "136") (name "unconnected-(H1-Pad33)") (class "Default")
      (node (ref "H1") (pin "33") (pinfunction "33_33") (pintype "passive"))
    )
    (net (code "137") (name "unconnected-(H1-Pad34)") (class "Default")
      (node (ref "H1") (pin "34") (pinfunction "34_34") (pintype "passive"))
    )
    (net (code "138") (name "unconnected-(H1-Pad35)") (class "Default")
      (node (ref "H1") (pin "35") (pinfunction "35_35") (pintype "passive"))
    )
    (net (code "139") (name "unconnected-(H1-Pad36)") (class "Default")
      (node (ref "H1") (pin "36") (pinfunction "36_36") (pintype "passive"))
    )
    (net (code "140") (name "unconnected-(H1-Pad37)") (class "Default")
      (node (ref "H1") (pin "37") (pinfunction "37_37") (pintype "passive"))
    )
    (net (code "141") (name "unconnected-(H1-Pad38)") (class "Default")
      (node (ref "H1") (pin "38") (pinfunction "38_38") (pintype "passive"))
    )
    (net (code "142") (name "unconnected-(H1-Pad39)") (class "Default")
      (node (ref "H1") (pin "39") (pinfunction "39_39") (pintype "passive"))
    )
    (net (code "143") (name "unconnected-(H1-Pad40)") (class "Default")
      (node (ref "H1") (pin "40") (pinfunction "40_40") (pintype "passive"))
    )
    (net (code "144") (name "unconnected-(H1-Pad41)") (class "Default")
      (node (ref "H1") (pin "41") (pinfunction "41_41") (pintype "passive"))
    )
    (net (code "145") (name "unconnected-(H1-Pad42)") (class "Default")
      (node (ref "H1") (pin "42") (pinfunction "42_42") (pintype "passive"))
    )
    (net (code "146") (name "unconnected-(H1-Pad43)") (class "Default")
      (node (ref "H1") (pin "43") (pinfunction "43_43") (pintype "passive"))
    )
    (net (code "147") (name "unconnected-(H1-Pad44)") (class "Default")
      (node (ref "H1") (pin "44") (pinfunction "44_44") (pintype "passive"))
    )
    (net (code "148") (name "unconnected-(H1-Pad45)") (class "Default")
      (node (ref "H1") (pin "45") (pinfunction "45_45") (pintype "passive"))
    )
    (net (code "149") (name "unconnected-(H1-Pad46)") (class "Default")
      (node (ref "H1") (pin "46") (pinfunction "46_46") (pintype "passive"))
    )
    (net (code "150") (name "unconnected-(H1-Pad47)") (class "Default")
      (node (ref "H1") (pin "47") (pinfunction "47_47") (pintype "passive"))
    )
    (net (code "151") (name "unconnected-(H1-Pad48)") (class "Default")
      (node (ref "H1") (pin "48") (pinfunction "48_48") (pintype "passive"))
    )
    (net (code "152") (name "unconnected-(H2-Pad19)") (class "Default")
      (node (ref "H2") (pin "19") (pinfunction "19_19") (pintype "passive"))
    )
    (net (code "153") (name "unconnected-(H2-Pad20)") (class "Default")
      (node (ref "H2") (pin "20") (pinfunction "20_20") (pintype "passive"))
    )
    (net (code "154") (name "unconnected-(H2-Pad23)") (class "Default")
      (node (ref "H2") (pin "23") (pinfunction "23_23") (pintype "passive"))
    )
    (net (code "155") (name "unconnected-(H2-Pad24)") (class "Default")
      (node (ref "H2") (pin "24") (pinfunction "24_24") (pintype "passive"))
    )
    (net (code "156") (name "unconnected-(H2-Pad25)") (class "Default")
      (node (ref "H2") (pin "25") (pinfunction "25_25") (pintype "passive"))
    )
    (net (code "157") (name "unconnected-(H2-Pad26)") (class "Default")
      (node (ref "H2") (pin "26") (pinfunction "26_26") (pintype "passive"))
    )
    (net (code "158") (name "unconnected-(H2-Pad27)") (class "Default")
      (node (ref "H2") (pin "27") (pinfunction "27_27") (pintype "passive"))
    )
    (net (code "159") (name "unconnected-(H2-Pad28)") (class "Default")
      (node (ref "H2") (pin "28") (pinfunction "28_28") (pintype "passive"))
    )
    (net (code "160") (name "unconnected-(H2-Pad29)") (class "Default")
      (node (ref "H2") (pin "29") (pinfunction "29_29") (pintype "passive"))
    )
    (net (code "161") (name "unconnected-(H2-Pad30)") (class "Default")
      (node (ref "H2") (pin "30") (pinfunction "30_30") (pintype "passive"))
    )
    (net (code "162") (name "unconnected-(H2-Pad31)") (class "Default")
      (node (ref "H2") (pin "31") (pinfunction "31_31") (pintype "passive"))
    )
    (net (code "163") (name "unconnected-(H2-Pad32)") (class "Default")
      (node (ref "H2") (pin "32") (pinfunction "32_32") (pintype "passive"))
    )
    (net (code "164") (name "unconnected-(H2-Pad33)") (class "Default")
      (node (ref "H2") (pin "33") (pinfunction "33_33") (pintype "passive"))
    )
    (net (code "165") (name "unconnected-(H2-Pad34)") (class "Default")
      (node (ref "H2") (pin "34") (pinfunction "34_34") (pintype "passive"))
    )
    (net (code "166") (name "unconnected-(H2-Pad35)") (class "Default")
      (node (ref "H2") (pin "35") (pinfunction "35_35") (pintype "passive"))
    )
    (net (code "167") (name "unconnected-(H2-Pad36)") (class "Default")
      (node (ref "H2") (pin "36") (pinfunction "36_36") (pintype "passive"))
    )
    (net (code "168") (name "unconnected-(H2-Pad37)") (class "Default")
      (node (ref "H2") (pin "37") (pinfunction "37_37") (pintype "passive"))
    )
    (net (code "169") (name "unconnected-(H2-Pad38)") (class "Default")
      (node (ref "H2") (pin "38") (pinfunction "38_38") (pintype "passive"))
    )
    (net (code "170") (name "unconnected-(H2-Pad39)") (class "Default")
      (node (ref "H2") (pin "39") (pinfunction "39_39") (pintype "passive"))
    )
    (net (code "171") (name "unconnected-(H2-Pad40)") (class "Default")
      (node (ref "H2") (pin "40") (pinfunction "40_40") (pintype "passive"))
    )
    (net (code "172") (name "unconnected-(H2-Pad41)") (class "Default")
      (node (ref "H2") (pin "41") (pinfunction "41_41") (pintype "passive"))
    )
    (net (code "173") (name "unconnected-(H2-Pad42)") (class "Default")
      (node (ref "H2") (pin "42") (pinfunction "42_42") (pintype "passive"))
    )
    (net (code "174") (name "unconnected-(H2-Pad43)") (class "Default")
      (node (ref "H2") (pin "43") (pinfunction "43_43") (pintype "passive"))
    )
    (net (code "175") (name "unconnected-(H2-Pad44)") (class "Default")
      (node (ref "H2") (pin "44") (pinfunction "44_44") (pintype "passive"))
    )
    (net (code "176") (name "unconnected-(H2-Pad45)") (class "Default")
      (node (ref "H2") (pin "45") (pinfunction "45_45") (pintype "passive"))
    )
    (net (code "177") (name "unconnected-(H2-Pad46)") (class "Default")
      (node (ref "H2") (pin "46") (pinfunction "46_46") (pintype "passive"))
    )
    (net (code "178") (name "unconnected-(H2-Pad47)") (class "Default")
      (node (ref "H2") (pin "47") (pinfunction "47_47") (pintype "passive"))
    )
    (net (code "179") (name "unconnected-(H2-Pad48)") (class "Default")
      (node (ref "H2") (pin "48") (pinfunction "48_48") (pintype "passive"))
    )
    (net (code "180") (name "unconnected-(U9-2Y-Pad5)") (class "Default")
      (node (ref "U9") (pin "5") (pinfunction "2Y_5") (pintype "output"))
    )
    (net (code "181") (name "unconnected-(U9-3Y-Pad2)") (class "Default")
      (node (ref "U9") (pin "2") (pinfunction "3Y_2") (pintype "output"))
    )
    (net (code "182") (name "unconnected-(U10-2Y-Pad5)") (class "Default")
      (node (ref "U10") (pin "5") (pinfunction "2Y_5") (pintype "output"))
    )
    (net (code "183") (name "unconnected-(U10-3Y-Pad2)") (class "Default")
      (node (ref "U10") (pin "2") (pinfunction "3Y_2") (pintype "output"))
    )
    (net (code "184") (name "unconnected-(X2-Pad10)") (class "Default")
      (node (ref "X2") (pin "10") (pinfunction "10_10") (pintype "passive"))
    )
  )
)
